# brd-relays.net
KiCad netlist of a schematic drawn in EAGLE
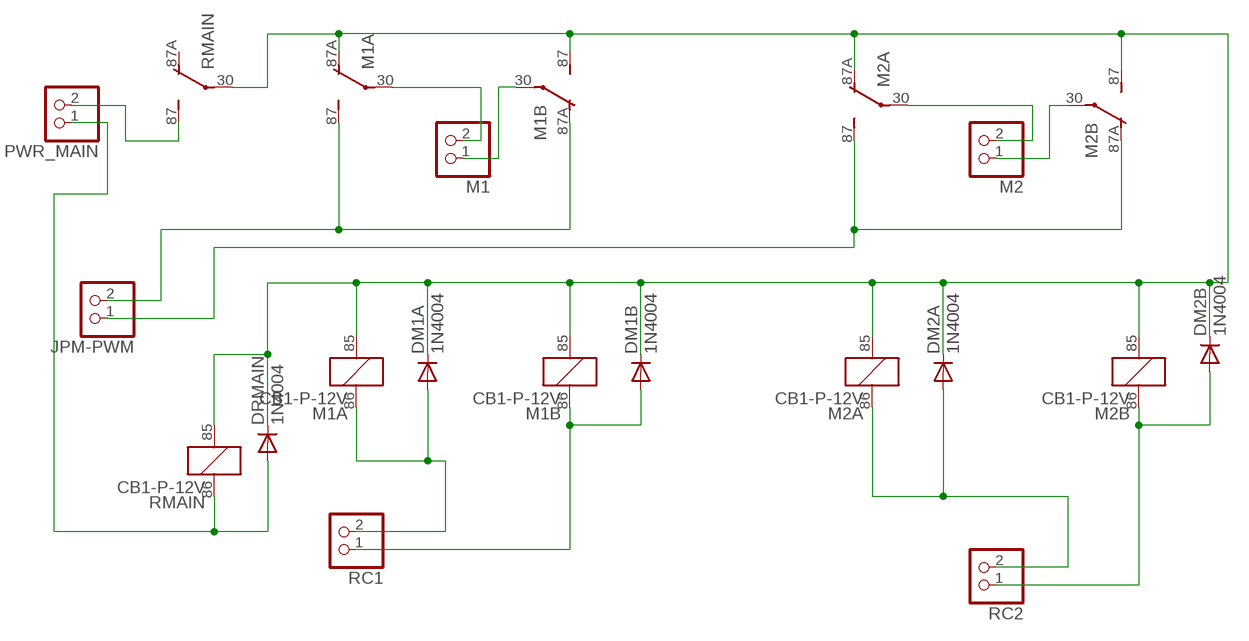
[diagram p0: schematic, sheet 1]

(export (version "E")
  (design (tool "Eeschema 10.0.6"))
  (components
    (comp (ref "DM1A")
      (value "1N4004")
      (footprint "eagle-import:DO41-10")
      (libsource (lib "eagle-import") (part "1N4004"))
    )
    (comp (ref "DM1B")
      (value "1N4004")
      (footprint "eagle-import:DO41-10")
      (libsource (lib "eagle-import") (part "1N4004"))
    )
    (comp (ref "DM2A")
      (value "1N4004")
      (footprint "eagle-import:DO41-10")
      (libsource (lib "eagle-import") (part "1N4004"))
    )
    (comp (ref "DM2B")
      (value "1N4004")
      (footprint "eagle-import:DO41-10")
      (libsource (lib "eagle-import") (part "1N4004"))
    )
    (comp (ref "DRMAIN")
      (value "1N4004")
      (footprint "eagle-import:DO41-10")
      (libsource (lib "eagle-import") (part "1N4004"))
    )
    (comp (ref "JPM-PWM")
      (value "PINHD-1X22X1-BIG")
      (footprint "eagle-import:1X02")
      (libsource (lib "eagle-import") (part "PINHD-1X22X1-BIG"))
    )
    (comp (ref "M1")
      (value "PINHD-1X22X1-BIG")
      (footprint "eagle-import:1X02")
      (libsource (lib "eagle-import") (part "PINHD-1X22X1-BIG"))
    )
    (comp (ref "M1A")
      (value "CB1-P-12V")
      (footprint "eagle-import:CB1")
      (fields (field (name "MF") "AROMAT/ MATSUSHITA"))
      (libsource (lib "eagle-import") (part "CB1-P-12V"))
    )
    (comp (ref "M1B")
      (value "CB1-P-12V")
      (footprint "eagle-import:CB1")
      (fields (field (name "MF") "AROMAT/ MATSUSHITA"))
      (libsource (lib "eagle-import") (part "CB1-P-12V"))
    )
    (comp (ref "M2")
      (value "PINHD-1X22X1-BIG")
      (footprint "eagle-import:1X02")
      (libsource (lib "eagle-import") (part "PINHD-1X22X1-BIG"))
    )
    (comp (ref "M2A")
      (value "CB1-P-12V")
      (footprint "eagle-import:CB1")
      (fields (field (name "MF") "AROMAT/ MATSUSHITA"))
      (libsource (lib "eagle-import") (part "CB1-P-12V"))
    )
    (comp (ref "M2B")
      (value "CB1-P-12V")
      (footprint "eagle-import:CB1")
      (fields (field (name "MF") "AROMAT/ MATSUSHITA"))
      (libsource (lib "eagle-import") (part "CB1-P-12V"))
    )
    (comp (ref "PWR_MAIN")
      (value "PINHD-1X22X1-BIG")
      (footprint "eagle-import:1X02")
      (libsource (lib "eagle-import") (part "PINHD-1X22X1-BIG"))
    )
    (comp (ref "RC1")
      (value "PINHD-1X22X1-BIG")
      (footprint "eagle-import:1X02")
      (libsource (lib "eagle-import") (part "PINHD-1X22X1-BIG"))
    )
    (comp (ref "RC2")
      (value "PINHD-1X22X1-BIG")
      (footprint "eagle-import:1X02")
      (libsource (lib "eagle-import") (part "PINHD-1X22X1-BIG"))
    )
    (comp (ref "RMAIN")
      (value "CB1-P-12V")
      (footprint "eagle-import:CB1")
      (fields (field (name "MF") "AROMAT/ MATSUSHITA"))
      (libsource (lib "eagle-import") (part "CB1-P-12V"))
    )
  )
  (nets
    (net (code "1") (name "Net-(M1AA-1)") (class "Default")
      (node (ref "DM1A") (pin "A") (pinfunction "A_A") (pintype "passive"))
      (node (ref "M1A") (pin "86") (pinfunction "1_86") (pintype "passive"))
      (node (ref "RC1") (pin "2") (pinfunction "2_2") (pintype "passive"))
    )
    (net (code "2") (name "Net-(M1AA-2)") (class "Default")
      (node (ref "DM1A") (pin "C") (pinfunction "C_C") (pintype "passive"))
      (node (ref "DM1B") (pin "C") (pinfunction "C_C") (pintype "passive"))
      (node (ref "DM2A") (pin "C") (pinfunction "C_C") (pintype "passive"))
      (node (ref "DM2B") (pin "C") (pinfunction "C_C") (pintype "passive"))
      (node (ref "DRMAIN") (pin "C") (pinfunction "C_C") (pintype "passive"))
      (node (ref "M1A") (pin "85") (pinfunction "2_85") (pintype "passive"))
      (node (ref "M1A") (pin "87A") (pinfunction "O_87A") (pintype "passive"))
      (node (ref "M1B") (pin "85") (pinfunction "2_85") (pintype "passive"))
      (node (ref "M1B") (pin "87") (pinfunction "S_87") (pintype "passive"))
      (node (ref "M2A") (pin "85") (pinfunction "2_85") (pintype "passive"))
      (node (ref "M2A") (pin "87A") (pinfunction "O_87A") (pintype "passive"))
      (node (ref "M2B") (pin "85") (pinfunction "2_85") (pintype "passive"))
      (node (ref "M2B") (pin "87") (pinfunction "S_87") (pintype "passive"))
      (node (ref "RMAIN") (pin "30") (pinfunction "P_30") (pintype "passive"))
      (node (ref "RMAIN") (pin "85") (pinfunction "2_85") (pintype "passive"))
    )
    (net (code "3") (name "Net-(M1AB-P)") (class "Default")
      (node (ref "M1") (pin "2") (pinfunction "2_2") (pintype "passive"))
      (node (ref "M1A") (pin "30") (pinfunction "P_30") (pintype "passive"))
    )
    (net (code "4") (name "Net-(M1AB-S)") (class "Default")
      (node (ref "JPM-PWM") (pin "2") (pinfunction "2_2") (pintype "passive"))
      (node (ref "M1A") (pin "87") (pinfunction "S_87") (pintype "passive"))
      (node (ref "M1B") (pin "87A") (pinfunction "O_87A") (pintype "passive"))
    )
    (net (code "5") (name "Net-(M1BA-1)") (class "Default")
      (node (ref "DM1B") (pin "A") (pinfunction "A_A") (pintype "passive"))
      (node (ref "M1B") (pin "86") (pinfunction "1_86") (pintype "passive"))
      (node (ref "RC1") (pin "1") (pinfunction "1_1") (pintype "passive"))
    )
    (net (code "6") (name "Net-(M1BB-P)") (class "Default")
      (node (ref "M1") (pin "1") (pinfunction "1_1") (pintype "passive"))
      (node (ref "M1B") (pin "30") (pinfunction "P_30") (pintype "passive"))
    )
    (net (code "7") (name "Net-(M2AA-1)") (class "Default")
      (node (ref "DM2A") (pin "A") (pinfunction "A_A") (pintype "passive"))
      (node (ref "M2A") (pin "86") (pinfunction "1_86") (pintype "passive"))
      (node (ref "RC2") (pin "2") (pinfunction "2_2") (pintype "passive"))
    )
    (net (code "8") (name "Net-(M2AB-P)") (class "Default")
      (node (ref "M2") (pin "2") (pinfunction "2_2") (pintype "passive"))
      (node (ref "M2A") (pin "30") (pinfunction "P_30") (pintype "passive"))
    )
    (net (code "9") (name "Net-(M2AB-S)") (class "Default")
      (node (ref "JPM-PWM") (pin "1") (pinfunction "1_1") (pintype "passive"))
      (node (ref "M2A") (pin "87") (pinfunction "S_87") (pintype "passive"))
      (node (ref "M2B") (pin "87A") (pinfunction "O_87A") (pintype "passive"))
    )
    (net (code "10") (name "Net-(M2BA-1)") (class "Default")
      (node (ref "DM2B") (pin "A") (pinfunction "A_A") (pintype "passive"))
      (node (ref "M2B") (pin "86") (pinfunction "1_86") (pintype "passive"))
      (node (ref "RC2") (pin "1") (pinfunction "1_1") (pintype "passive"))
    )
    (net (code "11") (name "Net-(M2BB-P)") (class "Default")
      (node (ref "M2") (pin "1") (pinfunction "1_1") (pintype "passive"))
      (node (ref "M2B") (pin "30") (pinfunction "P_30") (pintype "passive"))
    )
    (net (code "12") (name "Net-(RMAINA-1)") (class "Default")
      (node (ref "DRMAIN") (pin "A") (pinfunction "A_A") (pintype "passive"))
      (node (ref "PWR_MAIN") (pin "1") (pinfunction "1_1") (pintype "passive"))
      (node (ref "RMAIN") (pin "86") (pinfunction "1_86") (pintype "passive"))
    )
    (net (code "13") (name "Net-(RMAINB-S)") (class "Default")
      (node (ref "PWR_MAIN") (pin "2") (pinfunction "2_2") (pintype "passive"))
      (node (ref "RMAIN") (pin "87") (pinfunction "S_87") (pintype "passive"))
    )
    (net (code "14") (name "unconnected-(RMAINB-O-Pad87A)") (class "Default")
      (node (ref "RMAIN") (pin "87A") (pinfunction "O_87A") (pintype "passive"))
    )
  )
)
